# G221B.net
KiCad netlist of a schematic drawn in EAGLE
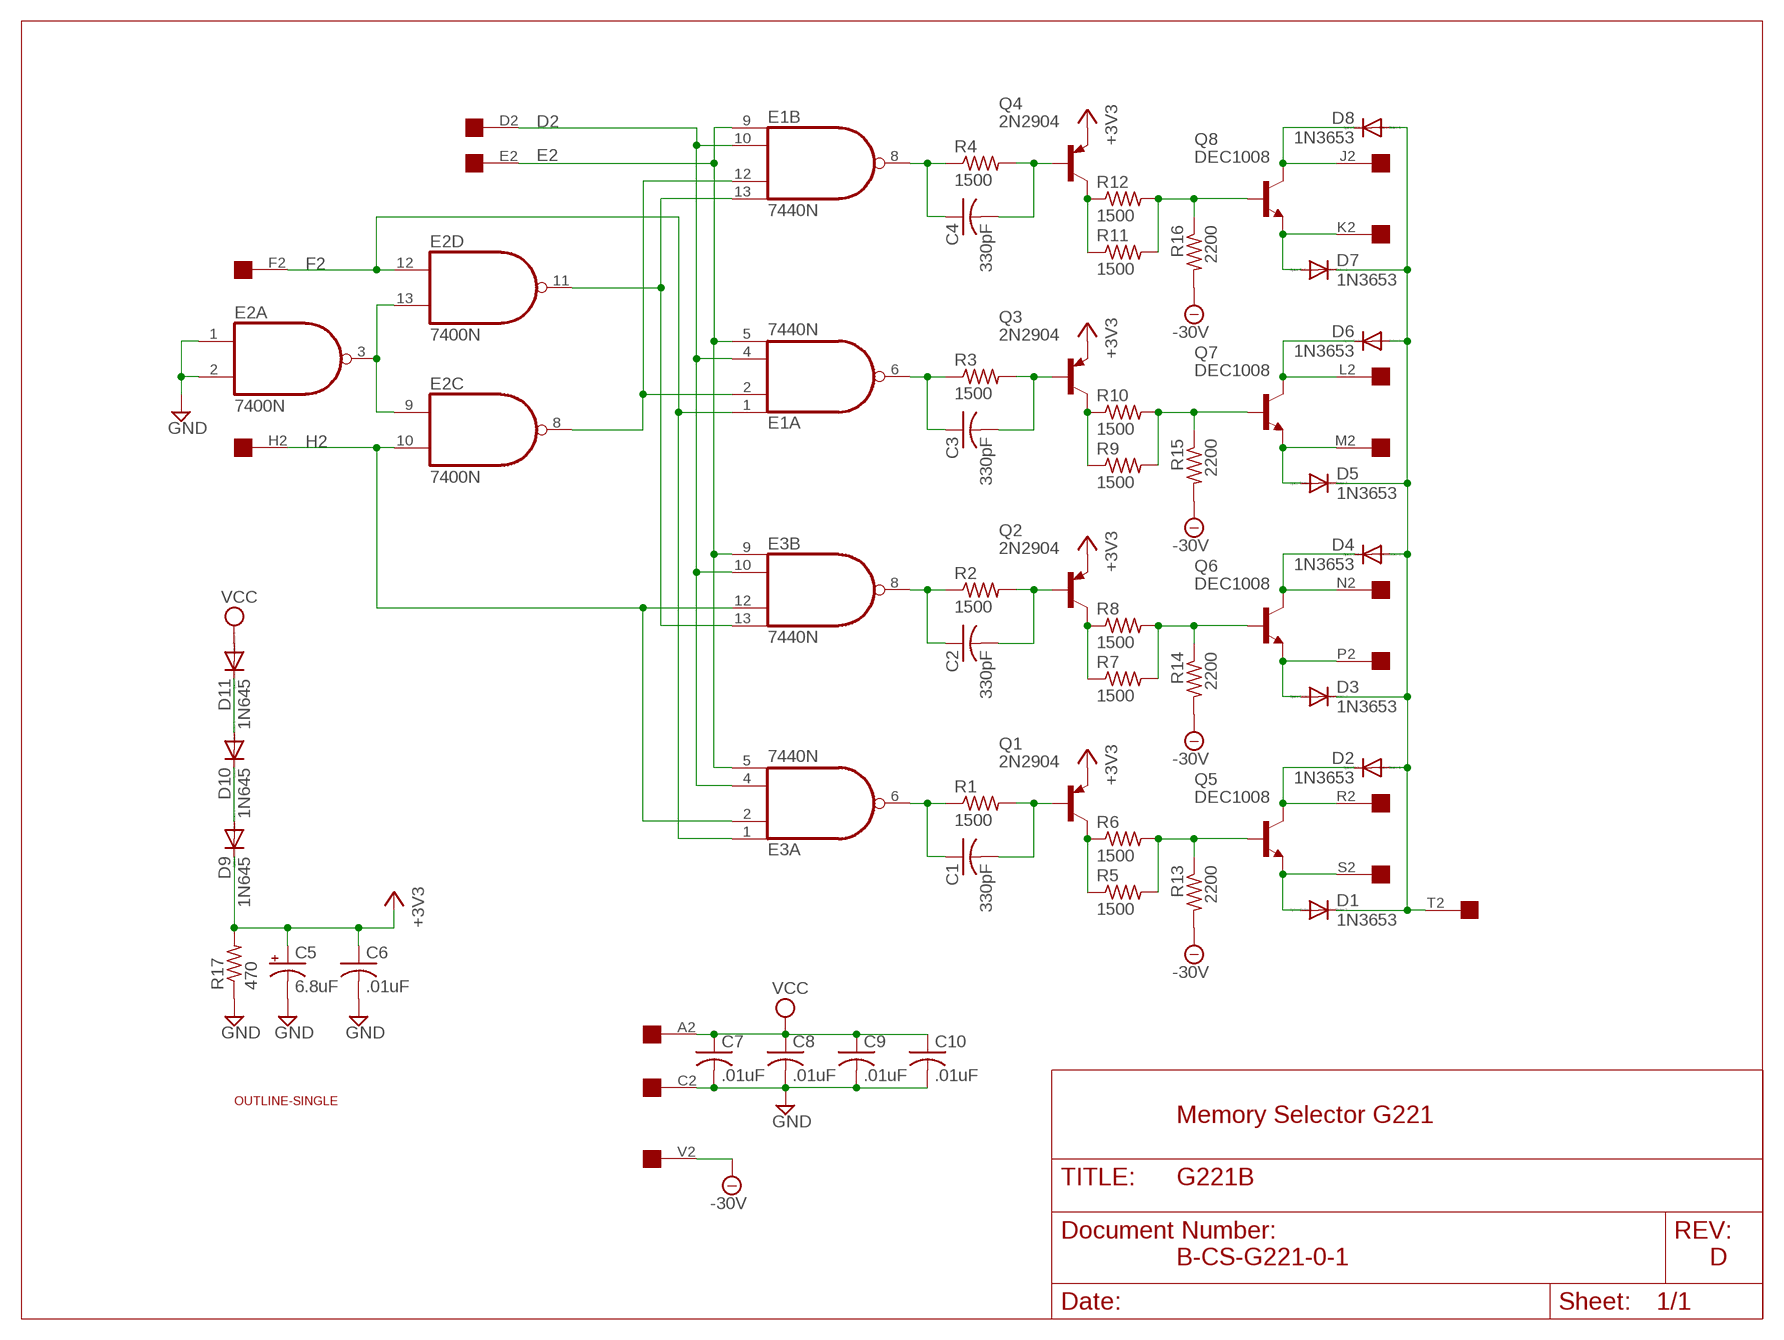
[diagram p0: schematic, sheet 1]

(export (version "E")
  (design (tool "Eeschema 10.0.6"))
  (components
    (comp (ref "C1")
      (value "330pF")
      (footprint "eagle-import:C050-025X075")
      (libsource (lib "eagle-import") (part "C-US050-025X075"))
    )
    (comp (ref "C2")
      (value "330pF")
      (footprint "eagle-import:C050-025X075")
      (libsource (lib "eagle-import") (part "C-US050-025X075"))
    )
    (comp (ref "C3")
      (value "330pF")
      (footprint "eagle-import:C050-025X075")
      (libsource (lib "eagle-import") (part "C-US050-025X075"))
    )
    (comp (ref "C4")
      (value "330pF")
      (footprint "eagle-import:C050-025X075")
      (libsource (lib "eagle-import") (part "C-US050-025X075"))
    )
    (comp (ref "C5")
      (value "6.8uF")
      (footprint "eagle-import:E12-8")
      (libsource (lib "eagle-import") (part "CPOL-USE20-8AXIAL"))
    )
    (comp (ref "C6")
      (value ".01uF")
      (footprint "eagle-import:C050-025X075")
      (libsource (lib "eagle-import") (part "C-US050-025X075"))
    )
    (comp (ref "C7")
      (value ".01uF")
      (footprint "eagle-import:C050-025X075")
      (libsource (lib "eagle-import") (part "C-US050-025X075"))
    )
    (comp (ref "C8")
      (value ".01uF")
      (footprint "eagle-import:C050-025X075")
      (libsource (lib "eagle-import") (part "C-US050-025X075"))
    )
    (comp (ref "C9")
      (value ".01uF")
      (footprint "eagle-import:C050-025X075")
      (libsource (lib "eagle-import") (part "C-US050-025X075"))
    )
    (comp (ref "C10")
      (value ".01uF")
      (footprint "eagle-import:C050-025X075")
      (libsource (lib "eagle-import") (part "C-US050-025X075"))
    )
    (comp (ref "D1")
      (value "1N3653")
      (footprint "eagle-import:DO35-10")
      (libsource (lib "eagle-import") (part "1N4148DO35-10"))
    )
    (comp (ref "D2")
      (value "1N3653")
      (footprint "eagle-import:DO35-10")
      (libsource (lib "eagle-import") (part "1N4148DO35-10"))
    )
    (comp (ref "D3")
      (value "1N3653")
      (footprint "eagle-import:DO35-10")
      (libsource (lib "eagle-import") (part "1N4148DO35-10"))
    )
    (comp (ref "D4")
      (value "1N3653")
      (footprint "eagle-import:DO35-10")
      (libsource (lib "eagle-import") (part "1N4148DO35-10"))
    )
    (comp (ref "D5")
      (value "1N3653")
      (footprint "eagle-import:DO35-10")
      (libsource (lib "eagle-import") (part "1N4148DO35-10"))
    )
    (comp (ref "D6")
      (value "1N3653")
      (footprint "eagle-import:DO35-10")
      (libsource (lib "eagle-import") (part "1N4148DO35-10"))
    )
    (comp (ref "D7")
      (value "1N3653")
      (footprint "eagle-import:DO35-10")
      (libsource (lib "eagle-import") (part "1N4148DO35-10"))
    )
    (comp (ref "D8")
      (value "1N3653")
      (footprint "eagle-import:DO35-10")
      (libsource (lib "eagle-import") (part "1N4148DO35-10"))
    )
    (comp (ref "D9")
      (value "1N645")
      (footprint "eagle-import:DO35-10")
      (libsource (lib "eagle-import") (part "1N4148DO35-10"))
    )
    (comp (ref "D10")
      (value "1N645")
      (footprint "eagle-import:DO35-10")
      (libsource (lib "eagle-import") (part "1N4148DO35-10"))
    )
    (comp (ref "D11")
      (value "1N645")
      (footprint "eagle-import:DO35-10")
      (libsource (lib "eagle-import") (part "1N4148DO35-10"))
    )
    (comp (ref "E1")
      (value "7440N")
      (footprint "eagle-import:DIL14")
      (libsource (lib "eagle-import") (part "7420NS"))
    )
    (comp (ref "E2")
      (value "7400N")
      (footprint "eagle-import:DIL14")
      (libsource (lib "eagle-import") (part "7400N"))
    )
    (comp (ref "E3")
      (value "7440N")
      (footprint "eagle-import:DIL14")
      (libsource (lib "eagle-import") (part "7420NS"))
    )
    (comp (ref "Q1")
      (value "2N2904")
      (footprint "eagle-import:TO39")
      (libsource (lib "eagle-import") (part "2N2904"))
    )
    (comp (ref "Q2")
      (value "2N2904")
      (footprint "eagle-import:TO39")
      (libsource (lib "eagle-import") (part "2N2904"))
    )
    (comp (ref "Q3")
      (value "2N2904")
      (footprint "eagle-import:TO39")
      (libsource (lib "eagle-import") (part "2N2904"))
    )
    (comp (ref "Q4")
      (value "2N2904")
      (footprint "eagle-import:TO39")
      (libsource (lib "eagle-import") (part "2N2904"))
    )
    (comp (ref "Q5")
      (value "DEC1008")
      (footprint "eagle-import:TO39")
      (libsource (lib "eagle-import") (part "-NPN-TO39-EBC2N1613"))
    )
    (comp (ref "Q6")
      (value "DEC1008")
      (footprint "eagle-import:TO39")
      (libsource (lib "eagle-import") (part "-NPN-TO39-EBC2N1613"))
    )
    (comp (ref "Q7")
      (value "DEC1008")
      (footprint "eagle-import:TO39")
      (libsource (lib "eagle-import") (part "-NPN-TO39-EBC2N1613"))
    )
    (comp (ref "Q8")
      (value "DEC1008")
      (footprint "eagle-import:TO39")
      (libsource (lib "eagle-import") (part "-NPN-TO39-EBC2N1613"))
    )
    (comp (ref "R1")
      (value "1500")
      (footprint "eagle-import:0207_10")
      (libsource (lib "eagle-import") (part "R-US_0207/10"))
    )
    (comp (ref "R2")
      (value "1500")
      (footprint "eagle-import:0207_10")
      (libsource (lib "eagle-import") (part "R-US_0207/10"))
    )
    (comp (ref "R3")
      (value "1500")
      (footprint "eagle-import:0207_10")
      (libsource (lib "eagle-import") (part "R-US_0207/10"))
    )
    (comp (ref "R4")
      (value "1500")
      (footprint "eagle-import:0207_10")
      (libsource (lib "eagle-import") (part "R-US_0207/10"))
    )
    (comp (ref "R5")
      (value "1500")
      (footprint "eagle-import:0207_10")
      (libsource (lib "eagle-import") (part "R-US_0207/10"))
    )
    (comp (ref "R6")
      (value "1500")
      (footprint "eagle-import:0207_10")
      (libsource (lib "eagle-import") (part "R-US_0207/10"))
    )
    (comp (ref "R7")
      (value "1500")
      (footprint "eagle-import:0207_10")
      (libsource (lib "eagle-import") (part "R-US_0207/10"))
    )
    (comp (ref "R8")
      (value "1500")
      (footprint "eagle-import:0207_10")
      (libsource (lib "eagle-import") (part "R-US_0207/10"))
    )
    (comp (ref "R9")
      (value "1500")
      (footprint "eagle-import:0207_10")
      (libsource (lib "eagle-import") (part "R-US_0207/10"))
    )
    (comp (ref "R10")
      (value "1500")
      (footprint "eagle-import:0207_10")
      (libsource (lib "eagle-import") (part "R-US_0207/10"))
    )
    (comp (ref "R11")
      (value "1500")
      (footprint "eagle-import:0207_10")
      (libsource (lib "eagle-import") (part "R-US_0207/10"))
    )
    (comp (ref "R12")
      (value "1500")
      (footprint "eagle-import:0207_10")
      (libsource (lib "eagle-import") (part "R-US_0207/10"))
    )
    (comp (ref "R13")
      (value "2200")
      (footprint "eagle-import:0207_10")
      (libsource (lib "eagle-import") (part "R-US_0207/10"))
    )
    (comp (ref "R14")
      (value "2200")
      (footprint "eagle-import:0207_10")
      (libsource (lib "eagle-import") (part "R-US_0207/10"))
    )
    (comp (ref "R15")
      (value "2200")
      (footprint "eagle-import:0207_10")
      (libsource (lib "eagle-import") (part "R-US_0207/10"))
    )
    (comp (ref "R16")
      (value "2200")
      (footprint "eagle-import:0207_10")
      (libsource (lib "eagle-import") (part "R-US_0207/10"))
    )
    (comp (ref "R17")
      (value "470")
      (footprint "eagle-import:0207_10")
      (libsource (lib "eagle-import") (part "R-US_0207/10"))
    )
    (comp (ref "U$1")
      (value "EDGE-1")
      (footprint "eagle-import:EDGE-CON1")
      (libsource (lib "eagle-import") (part "EDGE-1"))
    )
    (comp (ref "U$7")
      (value "OUTLINE-SINGLE")
      (footprint "eagle-import:SINGLE")
      (libsource (lib "eagle-import") (part "OUTLINE-SINGLE"))
    )
  )
  (nets
    (net (code "1") (name "+3V3") (class "Default")
      (node (ref "C5") (pin "+") (pinfunction "+_+") (pintype "passive"))
      (node (ref "C6") (pin "1") (pinfunction "1_1") (pintype "passive"))
      (node (ref "D9") (pin "C") (pinfunction "C_C") (pintype "passive"))
      (node (ref "Q1") (pin "1") (pinfunction "E_1") (pintype "passive"))
      (node (ref "Q2") (pin "1") (pinfunction "E_1") (pintype "passive"))
      (node (ref "Q3") (pin "1") (pinfunction "E_1") (pintype "passive"))
      (node (ref "Q4") (pin "1") (pinfunction "E_1") (pintype "passive"))
      (node (ref "R17") (pin "2") (pinfunction "2_2") (pintype "passive"))
    )
    (net (code "2") (name "-30V") (class "Default")
      (node (ref "R13") (pin "2") (pinfunction "2_2") (pintype "passive"))
      (node (ref "R14") (pin "2") (pinfunction "2_2") (pintype "passive"))
      (node (ref "R15") (pin "2") (pinfunction "2_2") (pintype "passive"))
      (node (ref "R16") (pin "2") (pinfunction "2_2") (pintype "passive"))
      (node (ref "U$1") (pin "V2") (pinfunction "1_V2") (pintype "bidirectional"))
    )
    (net (code "3") (name "/D2") (class "Default")
      (node (ref "E1") (pin "10") (pinfunction "I1_10") (pintype "input"))
      (node (ref "E1") (pin "4") (pinfunction "I2_4") (pintype "input"))
      (node (ref "E3") (pin "10") (pinfunction "I1_10") (pintype "input"))
      (node (ref "E3") (pin "4") (pinfunction "I2_4") (pintype "input"))
      (node (ref "U$1") (pin "D2") (pinfunction "1_D2") (pintype "bidirectional"))
    )
    (net (code "4") (name "/E2") (class "Default")
      (node (ref "E1") (pin "5") (pinfunction "I3_5") (pintype "input"))
      (node (ref "E1") (pin "9") (pinfunction "I0_9") (pintype "input"))
      (node (ref "E3") (pin "5") (pinfunction "I3_5") (pintype "input"))
      (node (ref "E3") (pin "9") (pinfunction "I0_9") (pintype "input"))
      (node (ref "U$1") (pin "E2") (pinfunction "1_E2") (pintype "bidirectional"))
    )
    (net (code "5") (name "/F2") (class "Default")
      (node (ref "E1") (pin "1") (pinfunction "I0_1") (pintype "input"))
      (node (ref "E2") (pin "12") (pinfunction "I0_12") (pintype "input"))
      (node (ref "E3") (pin "1") (pinfunction "I0_1") (pintype "input"))
      (node (ref "U$1") (pin "F2") (pinfunction "1_F2") (pintype "bidirectional"))
    )
    (net (code "6") (name "/H2") (class "Default")
      (node (ref "E2") (pin "10") (pinfunction "I1_10") (pintype "input"))
      (node (ref "E3") (pin "12") (pinfunction "I2_12") (pintype "input"))
      (node (ref "E3") (pin "2") (pinfunction "I1_2") (pintype "input"))
      (node (ref "U$1") (pin "H2") (pinfunction "1_H2") (pintype "bidirectional"))
    )
    (net (code "7") (name "GND") (class "Default")
      (node (ref "C10") (pin "2") (pinfunction "2_2") (pintype "passive"))
      (node (ref "C5") (pin "-") (pinfunction "-_-") (pintype "passive"))
      (node (ref "C6") (pin "2") (pinfunction "2_2") (pintype "passive"))
      (node (ref "C7") (pin "2") (pinfunction "2_2") (pintype "passive"))
      (node (ref "C8") (pin "2") (pinfunction "2_2") (pintype "passive"))
      (node (ref "C9") (pin "2") (pinfunction "2_2") (pintype "passive"))
      (node (ref "E2") (pin "1") (pinfunction "I0_1") (pintype "input"))
      (node (ref "E2") (pin "2") (pinfunction "I1_2") (pintype "input"))
      (node (ref "R17") (pin "1") (pinfunction "1_1") (pintype "passive"))
      (node (ref "U$1") (pin "C2") (pinfunction "1_C2") (pintype "bidirectional"))
    )
    (net (code "8") (name "Net-(D10-PadA)") (class "Default")
      (node (ref "D10") (pin "A") (pinfunction "A_A") (pintype "passive"))
      (node (ref "D11") (pin "C") (pinfunction "C_C") (pintype "passive"))
    )
    (net (code "9") (name "Net-(D10-PadC)") (class "Default")
      (node (ref "D10") (pin "C") (pinfunction "C_C") (pintype "passive"))
      (node (ref "D9") (pin "A") (pinfunction "A_A") (pintype "passive"))
    )
    (net (code "10") (name "Net-(E1A-I1)") (class "Default")
      (node (ref "E1") (pin "12") (pinfunction "I2_12") (pintype "input"))
      (node (ref "E1") (pin "2") (pinfunction "I1_2") (pintype "input"))
      (node (ref "E2") (pin "8") (pinfunction "O_8") (pintype "output"))
    )
    (net (code "11") (name "Net-(E1A-O)") (class "Default")
      (node (ref "C3") (pin "1") (pinfunction "1_1") (pintype "passive"))
      (node (ref "E1") (pin "6") (pinfunction "O_6") (pintype "output"))
      (node (ref "R3") (pin "1") (pinfunction "1_1") (pintype "passive"))
    )
    (net (code "12") (name "Net-(E1B-I3)") (class "Default")
      (node (ref "E1") (pin "13") (pinfunction "I3_13") (pintype "input"))
      (node (ref "E2") (pin "11") (pinfunction "O_11") (pintype "output"))
      (node (ref "E3") (pin "13") (pinfunction "I3_13") (pintype "input"))
    )
    (net (code "13") (name "Net-(E1B-O)") (class "Default")
      (node (ref "C4") (pin "1") (pinfunction "1_1") (pintype "passive"))
      (node (ref "E1") (pin "8") (pinfunction "O_8") (pintype "output"))
      (node (ref "R4") (pin "1") (pinfunction "1_1") (pintype "passive"))
    )
    (net (code "14") (name "Net-(E2A-O)") (class "Default")
      (node (ref "E2") (pin "13") (pinfunction "I1_13") (pintype "input"))
      (node (ref "E2") (pin "3") (pinfunction "O_3") (pintype "output"))
      (node (ref "E2") (pin "9") (pinfunction "I0_9") (pintype "input"))
    )
    (net (code "15") (name "Net-(E3A-O)") (class "Default")
      (node (ref "C1") (pin "1") (pinfunction "1_1") (pintype "passive"))
      (node (ref "E3") (pin "6") (pinfunction "O_6") (pintype "output"))
      (node (ref "R1") (pin "1") (pinfunction "1_1") (pintype "passive"))
    )
    (net (code "16") (name "Net-(E3B-O)") (class "Default")
      (node (ref "C2") (pin "1") (pinfunction "1_1") (pintype "passive"))
      (node (ref "E3") (pin "8") (pinfunction "O_8") (pintype "output"))
      (node (ref "R2") (pin "1") (pinfunction "1_1") (pintype "passive"))
    )
    (net (code "17") (name "Net-(Q1-B)") (class "Default")
      (node (ref "C1") (pin "2") (pinfunction "2_2") (pintype "passive"))
      (node (ref "Q1") (pin "2") (pinfunction "B_2") (pintype "passive"))
      (node (ref "R1") (pin "2") (pinfunction "2_2") (pintype "passive"))
    )
    (net (code "18") (name "Net-(Q1-C)") (class "Default")
      (node (ref "Q1") (pin "3") (pinfunction "C_3") (pintype "passive"))
      (node (ref "R5") (pin "1") (pinfunction "1_1") (pintype "passive"))
      (node (ref "R6") (pin "1") (pinfunction "1_1") (pintype "passive"))
    )
    (net (code "19") (name "Net-(Q2-B)") (class "Default")
      (node (ref "C2") (pin "2") (pinfunction "2_2") (pintype "passive"))
      (node (ref "Q2") (pin "2") (pinfunction "B_2") (pintype "passive"))
      (node (ref "R2") (pin "2") (pinfunction "2_2") (pintype "passive"))
    )
    (net (code "20") (name "Net-(Q2-C)") (class "Default")
      (node (ref "Q2") (pin "3") (pinfunction "C_3") (pintype "passive"))
      (node (ref "R7") (pin "1") (pinfunction "1_1") (pintype "passive"))
      (node (ref "R8") (pin "1") (pinfunction "1_1") (pintype "passive"))
    )
    (net (code "21") (name "Net-(Q3-B)") (class "Default")
      (node (ref "C3") (pin "2") (pinfunction "2_2") (pintype "passive"))
      (node (ref "Q3") (pin "2") (pinfunction "B_2") (pintype "passive"))
      (node (ref "R3") (pin "2") (pinfunction "2_2") (pintype "passive"))
    )
    (net (code "22") (name "Net-(Q3-C)") (class "Default")
      (node (ref "Q3") (pin "3") (pinfunction "C_3") (pintype "passive"))
      (node (ref "R10") (pin "1") (pinfunction "1_1") (pintype "passive"))
      (node (ref "R9") (pin "1") (pinfunction "1_1") (pintype "passive"))
    )
    (net (code "23") (name "Net-(Q4-B)") (class "Default")
      (node (ref "C4") (pin "2") (pinfunction "2_2") (pintype "passive"))
      (node (ref "Q4") (pin "2") (pinfunction "B_2") (pintype "passive"))
      (node (ref "R4") (pin "2") (pinfunction "2_2") (pintype "passive"))
    )
    (net (code "24") (name "Net-(Q4-C)") (class "Default")
      (node (ref "Q4") (pin "3") (pinfunction "C_3") (pintype "passive"))
      (node (ref "R11") (pin "1") (pinfunction "1_1") (pintype "passive"))
      (node (ref "R12") (pin "1") (pinfunction "1_1") (pintype "passive"))
    )
    (net (code "25") (name "Net-(Q5-B)") (class "Default")
      (node (ref "Q5") (pin "2") (pinfunction "B_2") (pintype "passive"))
      (node (ref "R13") (pin "1") (pinfunction "1_1") (pintype "passive"))
      (node (ref "R5") (pin "2") (pinfunction "2_2") (pintype "passive"))
      (node (ref "R6") (pin "2") (pinfunction "2_2") (pintype "passive"))
    )
    (net (code "26") (name "Net-(Q5-C)") (class "Default")
      (node (ref "D2") (pin "C") (pinfunction "C_C") (pintype "passive"))
      (node (ref "Q5") (pin "3") (pinfunction "C_3") (pintype "passive"))
      (node (ref "U$1") (pin "R2") (pinfunction "1_R2") (pintype "bidirectional"))
    )
    (net (code "27") (name "Net-(Q5-E)") (class "Default")
      (node (ref "D1") (pin "A") (pinfunction "A_A") (pintype "passive"))
      (node (ref "Q5") (pin "1") (pinfunction "E_1") (pintype "passive"))
      (node (ref "U$1") (pin "S2") (pinfunction "1_S2") (pintype "bidirectional"))
    )
    (net (code "28") (name "Net-(Q6-B)") (class "Default")
      (node (ref "Q6") (pin "2") (pinfunction "B_2") (pintype "passive"))
      (node (ref "R14") (pin "1") (pinfunction "1_1") (pintype "passive"))
      (node (ref "R7") (pin "2") (pinfunction "2_2") (pintype "passive"))
      (node (ref "R8") (pin "2") (pinfunction "2_2") (pintype "passive"))
    )
    (net (code "29") (name "Net-(Q6-C)") (class "Default")
      (node (ref "D4") (pin "C") (pinfunction "C_C") (pintype "passive"))
      (node (ref "Q6") (pin "3") (pinfunction "C_3") (pintype "passive"))
      (node (ref "U$1") (pin "N2") (pinfunction "1_N2") (pintype "bidirectional"))
    )
    (net (code "30") (name "Net-(Q6-E)") (class "Default")
      (node (ref "D3") (pin "A") (pinfunction "A_A") (pintype "passive"))
      (node (ref "Q6") (pin "1") (pinfunction "E_1") (pintype "passive"))
      (node (ref "U$1") (pin "P2") (pinfunction "1_P2") (pintype "bidirectional"))
    )
    (net (code "31") (name "Net-(Q7-B)") (class "Default")
      (node (ref "Q7") (pin "2") (pinfunction "B_2") (pintype "passive"))
      (node (ref "R10") (pin "2") (pinfunction "2_2") (pintype "passive"))
      (node (ref "R15") (pin "1") (pinfunction "1_1") (pintype "passive"))
      (node (ref "R9") (pin "2") (pinfunction "2_2") (pintype "passive"))
    )
    (net (code "32") (name "Net-(Q7-C)") (class "Default")
      (node (ref "D6") (pin "C") (pinfunction "C_C") (pintype "passive"))
      (node (ref "Q7") (pin "3") (pinfunction "C_3") (pintype "passive"))
      (node (ref "U$1") (pin "L2") (pinfunction "1_L2") (pintype "bidirectional"))
    )
    (net (code "33") (name "Net-(Q7-E)") (class "Default")
      (node (ref "D5") (pin "A") (pinfunction "A_A") (pintype "passive"))
      (node (ref "Q7") (pin "1") (pinfunction "E_1") (pintype "passive"))
      (node (ref "U$1") (pin "M2") (pinfunction "1_M2") (pintype "bidirectional"))
    )
    (net (code "34") (name "Net-(Q8-B)") (class "Default")
      (node (ref "Q8") (pin "2") (pinfunction "B_2") (pintype "passive"))
      (node (ref "R11") (pin "2") (pinfunction "2_2") (pintype "passive"))
      (node (ref "R12") (pin "2") (pinfunction "2_2") (pintype "passive"))
      (node (ref "R16") (pin "1") (pinfunction "1_1") (pintype "passive"))
    )
    (net (code "35") (name "Net-(Q8-C)") (class "Default")
      (node (ref "D8") (pin "C") (pinfunction "C_C") (pintype "passive"))
      (node (ref "Q8") (pin "3") (pinfunction "C_3") (pintype "passive"))
      (node (ref "U$1") (pin "J2") (pinfunction "1_J2") (pintype "bidirectional"))
    )
    (net (code "36") (name "Net-(Q8-E)") (class "Default")
      (node (ref "D7") (pin "A") (pinfunction "A_A") (pintype "passive"))
      (node (ref "Q8") (pin "1") (pinfunction "E_1") (pintype "passive"))
      (node (ref "U$1") (pin "K2") (pinfunction "1_K2") (pintype "bidirectional"))
    )
    (net (code "37") (name "Net-(U$1P-1)") (class "Default")
      (node (ref "D1") (pin "C") (pinfunction "C_C") (pintype "passive"))
      (node (ref "D2") (pin "A") (pinfunction "A_A") (pintype "passive"))
      (node (ref "D3") (pin "C") (pinfunction "C_C") (pintype "passive"))
      (node (ref "D4") (pin "A") (pinfunction "A_A") (pintype "passive"))
      (node (ref "D5") (pin "C") (pinfunction "C_C") (pintype "passive"))
      (node (ref "D6") (pin "A") (pinfunction "A_A") (pintype "passive"))
      (node (ref "D7") (pin "C") (pinfunction "C_C") (pintype "passive"))
      (node (ref "D8") (pin "A") (pinfunction "A_A") (pintype "passive"))
      (node (ref "U$1") (pin "T2") (pinfunction "1_T2") (pintype "bidirectional"))
    )
    (net (code "38") (name "VCC") (class "Default")
      (node (ref "C10") (pin "1") (pinfunction "1_1") (pintype "passive"))
      (node (ref "C7") (pin "1") (pinfunction "1_1") (pintype "passive"))
      (node (ref "C8") (pin "1") (pinfunction "1_1") (pintype "passive"))
      (node (ref "C9") (pin "1") (pinfunction "1_1") (pintype "passive"))
      (node (ref "D11") (pin "A") (pinfunction "A_A") (pintype "passive"))
      (node (ref "U$1") (pin "A2") (pinfunction "1_A2") (pintype "bidirectional"))
    )
  )
)
